# Transconductance.net
KiCad netlist of a schematic drawn in Altium Designer
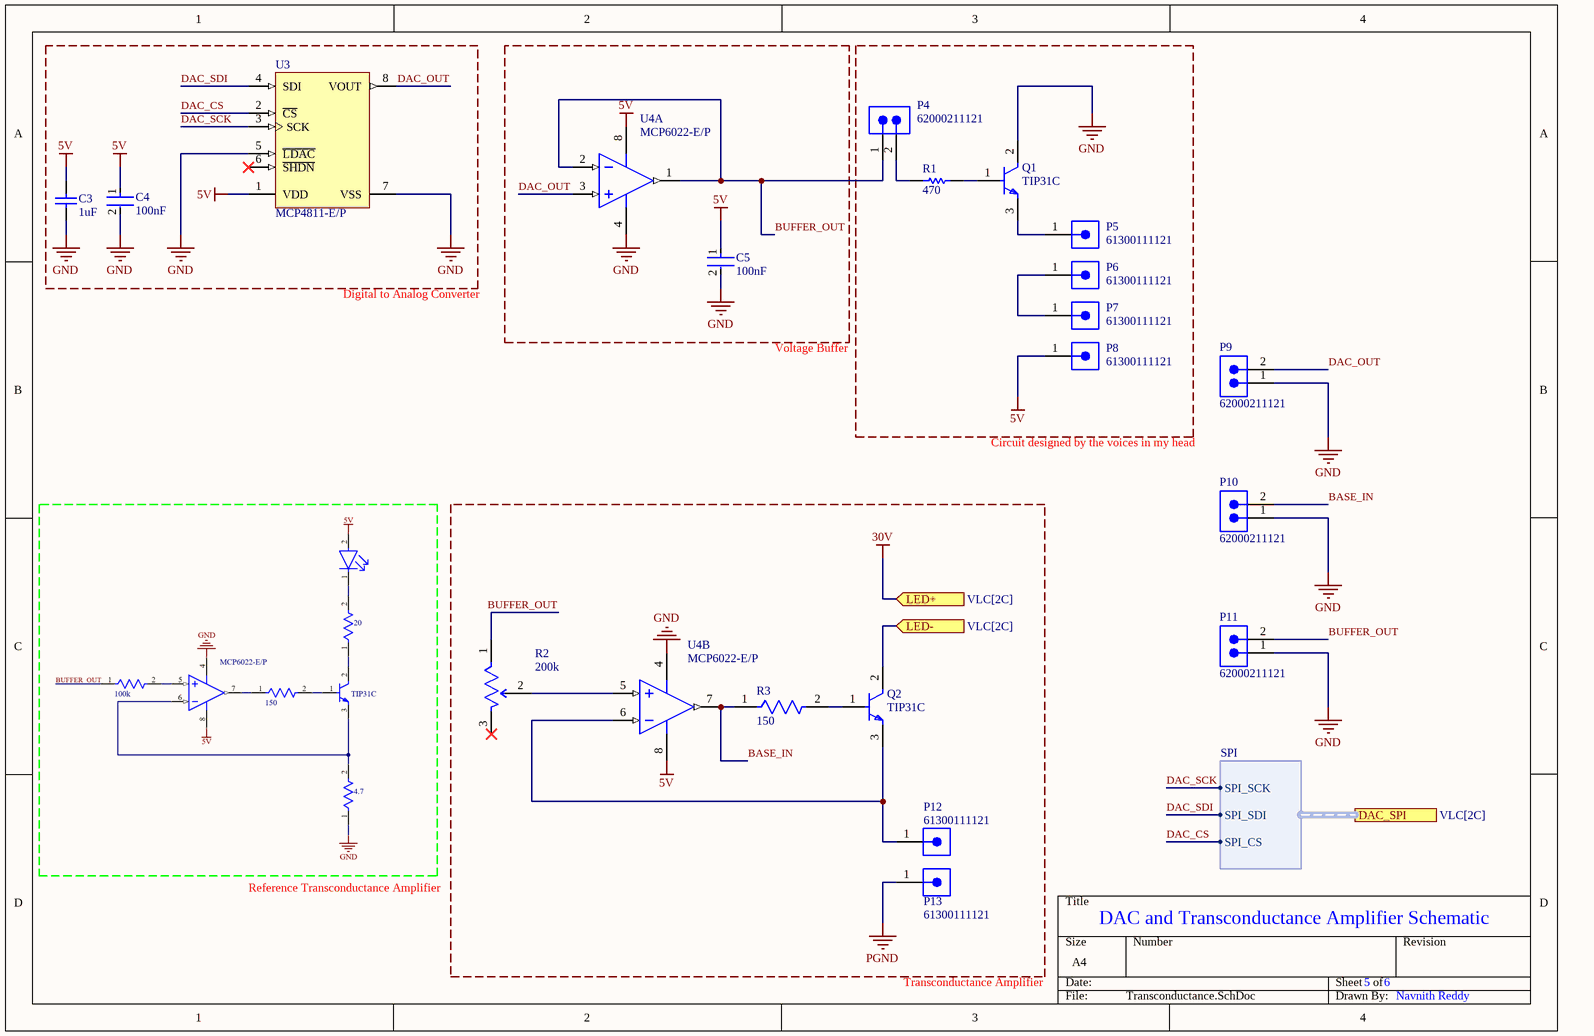
[diagram p0: Transconductance.SchDoc]

(export (version "E")
  (design (tool "Eeschema 10.0.6"))
  (components
    (comp (ref "C3")
      (value "1uF")
      (footprint "CAPC2013X145X50LL20T25")
      (fields (field (name "MANUFACTURER") "Kemet") (field (name "PART NUMBER") "C0805C105K4PACTU"))
      (libsource (lib "Altium Content Vault") (part "CAP"))
    )
    (comp (ref "C4")
      (value "100nF")
      (footprint "FP-C0805C-DN-MFG")
      (description "CAP CER 0.1UF 16V X7R 0805")
      (fields
        (field (name "OCTOPART") "https://octopart.com/c0805c104k4ractu-kemet-92155")
        (field (name "TOLERANCE") "0.1")
      )
      (libsource (lib "Altium Content Vault") (part "b4654b650e69147ec39a6b967a45e02"))
    )
    (comp (ref "C5")
      (value "100nF")
      (footprint "FP-C0805C-DN-MFG")
      (description "CAP CER 0.1UF 16V X7R 0805")
      (fields
        (field (name "OCTOPART") "https://octopart.com/c0805c104k4ractu-kemet-92155")
        (field (name "TOLERANCE") "0.1")
      )
      (libsource (lib "Altium Content Vault") (part "b4654b650e69147ec39a6b967a45e02"))
    )
    (comp (ref "P4")
      (value "62000211121")
      (footprint "62000211121")
      (libsource (lib "Altium Content Vault") (part "Header_Male_1R_02P"))
    )
    (comp (ref "P5")
      (value "61300111121")
      (footprint "61300111121")
      (libsource (lib "Altium Content Vault") (part "Header_Male_1R_01P"))
    )
    (comp (ref "P6")
      (value "61300111121")
      (footprint "61300111121")
      (libsource (lib "Altium Content Vault") (part "Header_Male_1R_01P"))
    )
    (comp (ref "P7")
      (value "61300111121")
      (footprint "61300111121")
      (libsource (lib "Altium Content Vault") (part "Header_Male_1R_01P"))
    )
    (comp (ref "P8")
      (value "61300111121")
      (footprint "61300111121")
      (libsource (lib "Altium Content Vault") (part "Header_Male_1R_01P"))
    )
    (comp (ref "P9")
      (value "62000211121")
      (footprint "62000211121")
      (libsource (lib "Altium Content Vault") (part "Header_Male_1R_02P"))
    )
    (comp (ref "P10")
      (value "62000211121")
      (footprint "62000211121")
      (libsource (lib "Altium Content Vault") (part "Header_Male_1R_02P"))
    )
    (comp (ref "P11")
      (value "62000211121")
      (footprint "62000211121")
      (libsource (lib "Altium Content Vault") (part "Header_Male_1R_02P"))
    )
    (comp (ref "P12")
      (value "61300111121")
      (footprint "61300111121")
      (libsource (lib "Altium Content Vault") (part "Header_Male_1R_01P"))
    )
    (comp (ref "P13")
      (value "61300111121")
      (footprint "61300111121")
      (libsource (lib "Altium Content Vault") (part "Header_Male_1R_01P"))
    )
    (comp (ref "Q1")
      (value "TIP31C")
      (footprint "FP-TO-220-P0A0015988-MFG")
      (description "TRANS NPN 100V 3A TO-220")
      (fields
        (field (name "OCTOPART") "https://octopart.com/tip31c-stmicroelectronics-15555")
        (field (name "MANUFACTURER") "STMicroelectronics")
      )
      (libsource (lib "Altium Content Vault") (part "1c57d9dae74fe2702546667b0e849db"))
    )
    (comp (ref "Q2")
      (value "TIP31C")
      (footprint "FP-TO-220-P0A0015988-MFG")
      (description "TRANS NPN 100V 3A TO-220")
      (fields
        (field (name "OCTOPART") "https://octopart.com/tip31c-stmicroelectronics-15555")
        (field (name "MANUFACTURER") "STMicroelectronics")
      )
      (libsource (lib "Altium Content Vault") (part "1c57d9dae74fe2702546667b0e849db"))
    )
    (comp (ref "R1")
      (value "470")
      (footprint "RESC2013X50X30LL20T20")
      (fields (field (name "MANUFACTURER") "Vishay Dale") (field (name "PART NUMBER") "CRCW0805470RFKEA"))
      (libsource (lib "Altium Content Vault") (part "RES"))
    )
    (comp (ref "R2")
      (value "200k")
      (footprint "FP-3296W-MFG")
      (description "TRIMMER 200K OHM 0.5W PC PIN TOP")
      (fields (field (name "TOLERANCE") "10%"))
      (libsource (lib "Altium Content Vault") (part "2dcfd2547301a7d3209a5e99acfd772"))
    )
    (comp (ref "R3")
      (value "150")
      (footprint "FP-CRCW0805-e3-IPC_A")
      (description "RES Thick Film, 150Ω, 5%, 0.125W, 200ppm/°C, 0805")
      (fields (field (name "TOLERANCE") "5%"))
      (libsource (lib "Altium Content Vault") (part "1029c3af85768c4190bb7ad29bc67b5"))
    )
    (comp (ref "U3")
      (value "MCP4811-E/P")
      (footprint "PDIP300-P8")
      (description "10-Bit DACs with Internal VREF and SPI Interface, 8-Pin PDIP, Extended Temperature")
      (libsource (lib "Altium Content Vault") (part "CON-DAC-MCP4821-8"))
    )
    (comp (ref "U4")
      (value "MCP6022-E/P")
      (footprint "PDIP300-P8")
      (description "None")
      (libsource (lib "Altium Content Vault") (part "AMP-OPA-MCP6022-IL8"))
    )
  )
  (nets
    (net (code "2") (name "/BASE_IN") (class "Default")
      (node (ref "P10") (pin "2") (pinfunction "2_2") (pintype "passive"))
      (node (ref "R3") (pin "1") (pinfunction "1_1") (pintype "passive"))
      (node (ref "U4") (pin "7") (pinfunction "VOUTB_7") (pintype "output"))
    )
    (net (code "3") (name "/BUFFER_OUT") (class "Default")
      (node (ref "P11") (pin "2") (pinfunction "2_2") (pintype "passive"))
      (node (ref "P4") (pin "1") (pinfunction "1_1") (pintype "passive"))
      (node (ref "R2") (pin "1") (pinfunction "CCW_1") (pintype "passive"))
      (node (ref "U4") (pin "1") (pinfunction "VOUTA_1") (pintype "output"))
      (node (ref "U4") (pin "2") (pinfunction "VINA-_2") (pintype "input"))
    )
    (net (code "4") (name "/DAC_CS") (class "Default")
      (node (ref "U3") (pin "2") (pinfunction "~{CS}_2") (pintype "input"))
    )
    (net (code "5") (name "/DAC_OUT") (class "Default")
      (node (ref "P9") (pin "2") (pinfunction "2_2") (pintype "passive"))
      (node (ref "U3") (pin "8") (pinfunction "VOUT_8") (pintype "output"))
      (node (ref "U4") (pin "3") (pinfunction "VINA+_3") (pintype "input"))
    )
    (net (code "6") (name "/DAC_SCK") (class "Default")
      (node (ref "U3") (pin "3") (pinfunction "SCK_3") (pintype "input"))
    )
    (net (code "7") (name "/DAC_SDI") (class "Default")
      (node (ref "U3") (pin "4") (pinfunction "SDI_4") (pintype "input"))
    )
    (net (code "8") (name "/LED-") (class "Default")
      (node (ref "Q2") (pin "2") (pinfunction "C_2") (pintype "passive"))
    )
    (net (code "10") (name "5V") (class "Default")
      (node (ref "C3") (pin "2") (pinfunction "2_2") (pintype "passive"))
      (node (ref "C4") (pin "1") (pinfunction "1_1") (pintype "passive"))
      (node (ref "C5") (pin "1") (pinfunction "1_1") (pintype "passive"))
      (node (ref "P8") (pin "1") (pinfunction "1_1") (pintype "passive"))
      (node (ref "U3") (pin "1") (pinfunction "VDD_1") (pintype "power_in"))
      (node (ref "U4") (pin "8") (pinfunction "VDD_8") (pintype "power_in"))
    )
    (net (code "12") (name "GND") (class "Default")
      (node (ref "C3") (pin "1") (pinfunction "1_1") (pintype "passive"))
      (node (ref "C4") (pin "2") (pinfunction "2_2") (pintype "passive"))
      (node (ref "C5") (pin "2") (pinfunction "2_2") (pintype "passive"))
      (node (ref "P10") (pin "1") (pinfunction "1_1") (pintype "passive"))
      (node (ref "P11") (pin "1") (pinfunction "1_1") (pintype "passive"))
      (node (ref "P9") (pin "1") (pinfunction "1_1") (pintype "passive"))
      (node (ref "Q1") (pin "2") (pinfunction "C_2") (pintype "passive"))
      (node (ref "U3") (pin "5") (pinfunction "~{LDAC}_5") (pintype "input"))
      (node (ref "U3") (pin "7") (pinfunction "VSS_7") (pintype "power_in"))
      (node (ref "U4") (pin "4") (pinfunction "VSS_4") (pintype "power_in"))
    )
    (net (code "13") (name "Net-(P4-Pad2)") (class "Default")
      (node (ref "P4") (pin "2") (pinfunction "2_2") (pintype "passive"))
      (node (ref "R1") (pin "1") (pinfunction "1_1") (pintype "passive"))
    )
    (net (code "14") (name "Net-(P6-Pad1)") (class "Default")
      (node (ref "P6") (pin "1") (pinfunction "1_1") (pintype "passive"))
      (node (ref "P7") (pin "1") (pinfunction "1_1") (pintype "passive"))
    )
    (net (code "15") (name "Net-(Q1-B)") (class "Default")
      (node (ref "Q1") (pin "1") (pinfunction "B_1") (pintype "passive"))
      (node (ref "R1") (pin "2") (pinfunction "2_2") (pintype "passive"))
    )
    (net (code "16") (name "Net-(Q1-E)") (class "Default")
      (node (ref "P5") (pin "1") (pinfunction "1_1") (pintype "passive"))
      (node (ref "Q1") (pin "3") (pinfunction "E_3") (pintype "passive"))
    )
    (net (code "17") (name "Net-(Q2-B)") (class "Default")
      (node (ref "Q2") (pin "1") (pinfunction "B_1") (pintype "passive"))
      (node (ref "R3") (pin "2") (pinfunction "2_2") (pintype "passive"))
    )
    (net (code "18") (name "Net-(Q2-E)") (class "Default")
      (node (ref "P12") (pin "1") (pinfunction "1_1") (pintype "passive"))
      (node (ref "Q2") (pin "3") (pinfunction "E_3") (pintype "passive"))
      (node (ref "U4") (pin "6") (pinfunction "VINB-_6") (pintype "input"))
    )
    (net (code "19") (name "Net-(R2-WIPER)") (class "Default")
      (node (ref "R2") (pin "2") (pinfunction "WIPER_2") (pintype "passive"))
      (node (ref "U4") (pin "5") (pinfunction "VINB+_5") (pintype "input"))
    )
    (net (code "20") (name "PGND") (class "Default")
      (node (ref "P13") (pin "1") (pinfunction "1_1") (pintype "passive"))
    )
    (net (code "21") (name "unconnected-(R2-CW-Pad3)") (class "Default")
      (node (ref "R2") (pin "3") (pinfunction "CW_3") (pintype "passive+no_connect"))
    )
    (net (code "22") (name "unconnected-(U3-~{SHDN}-Pad6)") (class "Default")
      (node (ref "U3") (pin "6") (pinfunction "~{SHDN}_6") (pintype "input+no_connect"))
    )
  )
)
